# EnCoder.net
KiCad netlist of a schematic drawn in Altium Designer
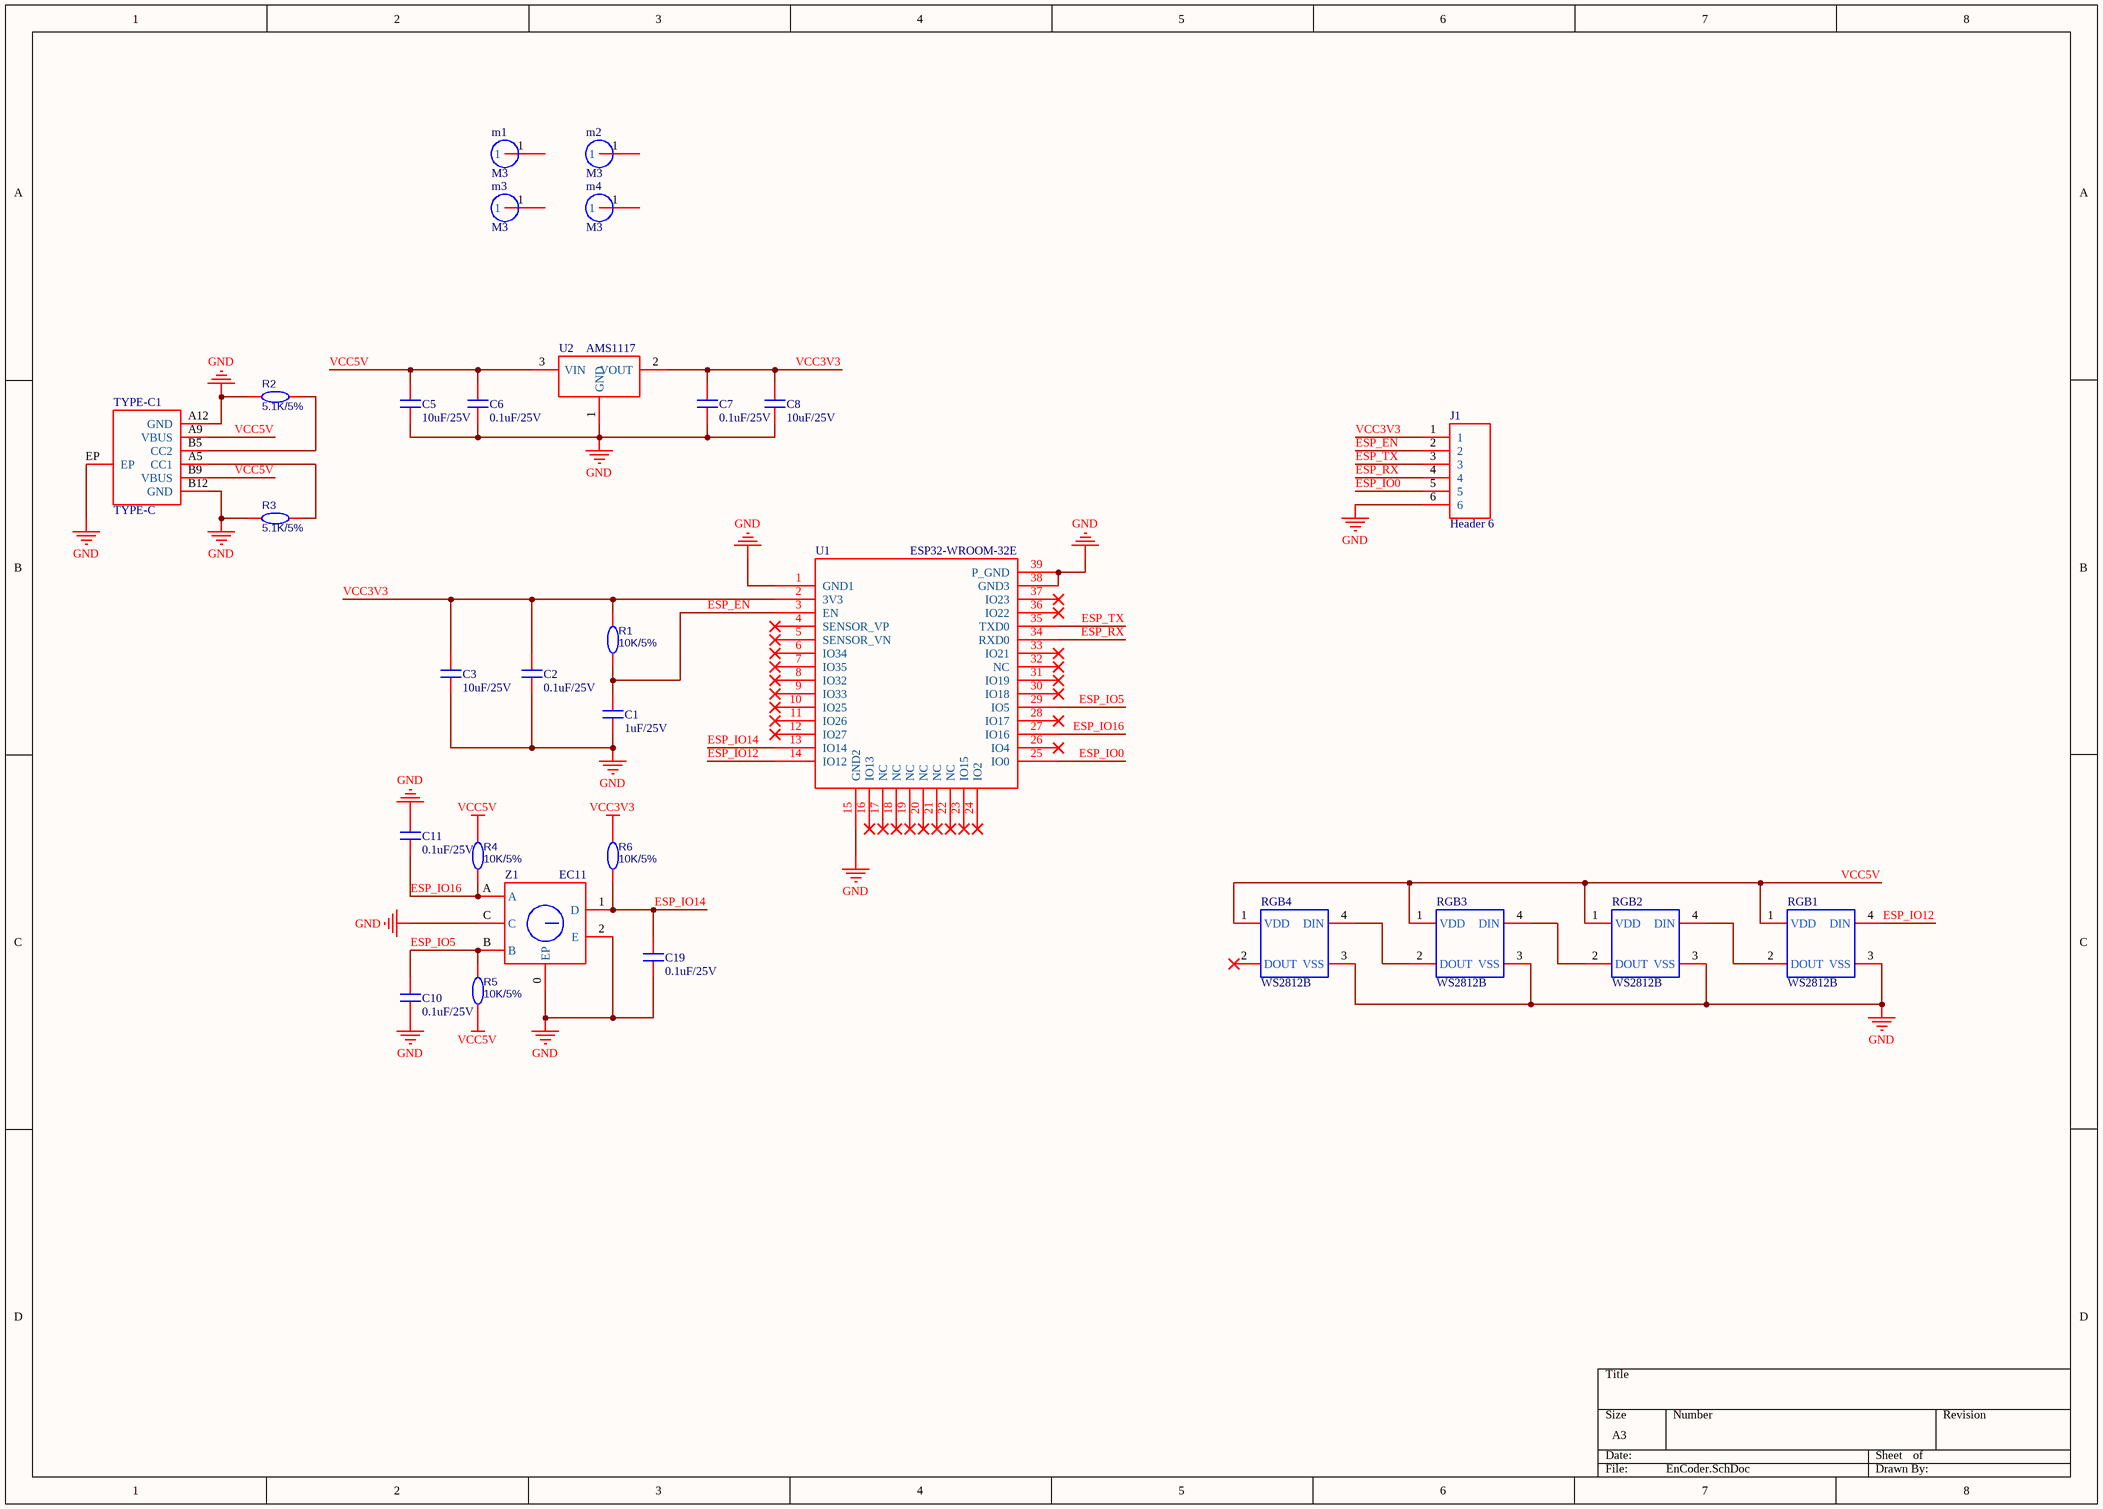
[diagram p0: EnCoder.SchDoc]

(export (version "E")
  (design (tool "Eeschema 10.0.6"))
  (components
    (comp (ref "C1")
      (value "1uF/25V")
      (footprint "C 0805B")
      (description "贴片电容")
      (libsource (lib "COYOO") (part "C 0805"))
    )
    (comp (ref "C2")
      (value "0.1uF/25V")
      (footprint "C 0805B")
      (description "贴片电容")
      (libsource (lib "COYOO") (part "C 0805"))
    )
    (comp (ref "C3")
      (value "10uF/25V")
      (footprint "C 0805B")
      (description "贴片电容")
      (libsource (lib "COYOO") (part "C 0805"))
    )
    (comp (ref "C5")
      (value "10uF/25V")
      (footprint "C 0805B")
      (description "贴片电容")
      (libsource (lib "COYOO") (part "C 0805"))
    )
    (comp (ref "C6")
      (value "0.1uF/25V")
      (footprint "C 0805B")
      (description "贴片电容")
      (libsource (lib "COYOO") (part "C 0805"))
    )
    (comp (ref "C7")
      (value "0.1uF/25V")
      (footprint "C 0805B")
      (description "贴片电容")
      (libsource (lib "COYOO") (part "C 0805"))
    )
    (comp (ref "C8")
      (value "10uF/25V")
      (footprint "C 0805B")
      (description "贴片电容")
      (libsource (lib "COYOO") (part "C 0805"))
    )
    (comp (ref "C10")
      (value "0.1uF/25V")
      (footprint "C 0805B")
      (description "贴片电容")
      (libsource (lib "COYOO") (part "C 0805"))
    )
    (comp (ref "C11")
      (value "0.1uF/25V")
      (footprint "C 0805B")
      (description "贴片电容")
      (libsource (lib "COYOO") (part "C 0805"))
    )
    (comp (ref "C19")
      (value "0.1uF/25V")
      (footprint "C 0805B")
      (description "贴片电容")
      (libsource (lib "COYOO") (part "C 0805"))
    )
    (comp (ref "J1")
      (value "Header 6")
      (footprint "Header6")
      (description "端子")
      (libsource (lib "COYOO") (part "Header 6"))
    )
    (comp (ref "m1") (value "M3") (footprint "M3") (description "M3螺丝") (libsource (lib "COYOO") (part "M3")))
    (comp (ref "m2") (value "M3") (footprint "M3") (description "M3螺丝") (libsource (lib "COYOO") (part "M3")))
    (comp (ref "m3") (value "M3") (footprint "M3") (description "M3螺丝") (libsource (lib "COYOO") (part "M3")))
    (comp (ref "m4") (value "M3") (footprint "M3") (description "M3螺丝") (libsource (lib "COYOO") (part "M3")))
    (comp (ref "R1")
      (value "10K/5%")
      (footprint "R 0805")
      (description "贴片电阻")
      (fields
        (field (name "BOM_MANUFACTURER PART") "RTT021202FTH")
        (field (name "BOM_SUPPLIER PART") "C102781")
      )
      (libsource (lib "COYOO") (part "R 0603"))
    )
    (comp (ref "R2")
      (value "5.1K/5%")
      (footprint "R 0805")
      (description "贴片电阻")
      (fields
        (field (name "BOM_MANUFACTURER PART") "RTT021202FTH")
        (field (name "BOM_SUPPLIER PART") "C102781")
      )
      (libsource (lib "COYOO") (part "R 0603"))
    )
    (comp (ref "R3")
      (value "5.1K/5%")
      (footprint "R 0805")
      (description "贴片电阻")
      (fields
        (field (name "BOM_MANUFACTURER PART") "RTT021202FTH")
        (field (name "BOM_SUPPLIER PART") "C102781")
      )
      (libsource (lib "COYOO") (part "R 0603"))
    )
    (comp (ref "R4")
      (value "10K/5%")
      (footprint "R 0805")
      (description "贴片电阻")
      (fields
        (field (name "BOM_MANUFACTURER PART") "RTT021202FTH")
        (field (name "BOM_SUPPLIER PART") "C102781")
      )
      (libsource (lib "COYOO") (part "R 0603"))
    )
    (comp (ref "R5")
      (value "10K/5%")
      (footprint "R 0805")
      (description "贴片电阻")
      (fields
        (field (name "BOM_MANUFACTURER PART") "RTT021202FTH")
        (field (name "BOM_SUPPLIER PART") "C102781")
      )
      (libsource (lib "COYOO") (part "R 0603"))
    )
    (comp (ref "R6")
      (value "10K/5%")
      (footprint "R 0805")
      (description "贴片电阻")
      (fields
        (field (name "BOM_MANUFACTURER PART") "RTT021202FTH")
        (field (name "BOM_SUPPLIER PART") "C102781")
      )
      (libsource (lib "COYOO") (part "R 0603"))
    )
    (comp (ref "RGB1")
      (value "WS2812B")
      (footprint "RGBLED5050-4")
      (description "WS2812B灯珠")
      (libsource (lib "COYOO") (part "WS2812B"))
    )
    (comp (ref "RGB2")
      (value "WS2812B")
      (footprint "RGBLED5050-4")
      (description "WS2812B灯珠")
      (libsource (lib "COYOO") (part "WS2812B"))
    )
    (comp (ref "RGB3")
      (value "WS2812B")
      (footprint "RGBLED5050-4")
      (description "WS2812B灯珠")
      (libsource (lib "COYOO") (part "WS2812B"))
    )
    (comp (ref "RGB4")
      (value "WS2812B")
      (footprint "RGBLED5050-4")
      (description "WS2812B灯珠")
      (libsource (lib "COYOO") (part "WS2812B"))
    )
    (comp (ref "TYPE-C1")
      (value "TYPE-C")
      (footprint "TYPE-C-6P")
      (libsource (lib "COYOO") (part "TYPE-C-6"))
    )
    (comp (ref "U1")
      (value "ESP32-WROOM-32E")
      (footprint "ESP32-WROOM-32E")
      (description "ESP32模块")
      (libsource (lib "COYOO") (part "ESP32-WROOM-32E"))
    )
    (comp (ref "U2")
      (value "AMS1117")
      (footprint "SOT223_L")
      (description "IC LDO")
      (libsource (lib "COYOO") (part "AMS1117"))
    )
    (comp (ref "Z1")
      (value "EC11")
      (footprint "EC11-SMD")
      (description "编码器")
      (libsource (lib "COYOO") (part "EC11"))
    )
  )
  (nets
    (net (code "1") (name "/ESP_EN") (class "Default")
      (node (ref "C1") (pin "2") (pinfunction "2_2") (pintype "passive"))
      (node (ref "J1") (pin "2") (pinfunction "2_2") (pintype "passive"))
      (node (ref "R1") (pin "1") (pinfunction "1_1") (pintype "passive"))
      (node (ref "U1") (pin "3") (pinfunction "EN_3") (pintype "passive"))
    )
    (net (code "2") (name "/ESP_IO0") (class "Default")
      (node (ref "J1") (pin "5") (pinfunction "5_5") (pintype "passive"))
      (node (ref "U1") (pin "25") (pinfunction "IO0_25") (pintype "passive"))
    )
    (net (code "3") (name "/ESP_IO5") (class "Default")
      (node (ref "C10") (pin "1") (pinfunction "1_1") (pintype "passive"))
      (node (ref "R5") (pin "1") (pinfunction "1_1") (pintype "passive"))
      (node (ref "U1") (pin "29") (pinfunction "IO5_29") (pintype "passive"))
      (node (ref "Z1") (pin "B") (pinfunction "B_B") (pintype "passive"))
    )
    (net (code "4") (name "/ESP_IO12") (class "Default")
      (node (ref "RGB1") (pin "4") (pinfunction "DIN_4") (pintype "passive"))
      (node (ref "U1") (pin "14") (pinfunction "IO12_14") (pintype "passive"))
    )
    (net (code "5") (name "/ESP_IO14") (class "Default")
      (node (ref "C19") (pin "1") (pinfunction "1_1") (pintype "passive"))
      (node (ref "R6") (pin "2") (pinfunction "2_2") (pintype "passive"))
      (node (ref "U1") (pin "13") (pinfunction "IO14_13") (pintype "passive"))
      (node (ref "Z1") (pin "1") (pinfunction "D_1") (pintype "passive"))
    )
    (net (code "6") (name "/ESP_IO16") (class "Default")
      (node (ref "C11") (pin "2") (pinfunction "2_2") (pintype "passive"))
      (node (ref "R4") (pin "2") (pinfunction "2_2") (pintype "passive"))
      (node (ref "U1") (pin "27") (pinfunction "IO16_27") (pintype "passive"))
      (node (ref "Z1") (pin "A") (pinfunction "A_A") (pintype "passive"))
    )
    (net (code "7") (name "/ESP_RX") (class "Default")
      (node (ref "J1") (pin "4") (pinfunction "4_4") (pintype "passive"))
      (node (ref "U1") (pin "34") (pinfunction "RXD0_34") (pintype "passive"))
    )
    (net (code "8") (name "/ESP_TX") (class "Default")
      (node (ref "J1") (pin "3") (pinfunction "3_3") (pintype "passive"))
      (node (ref "U1") (pin "35") (pinfunction "TXD0_35") (pintype "passive"))
    )
    (net (code "9") (name "GND") (class "Default")
      (node (ref "C1") (pin "1") (pinfunction "1_1") (pintype "passive"))
      (node (ref "C10") (pin "2") (pinfunction "2_2") (pintype "passive"))
      (node (ref "C11") (pin "1") (pinfunction "1_1") (pintype "passive"))
      (node (ref "C19") (pin "2") (pinfunction "2_2") (pintype "passive"))
      (node (ref "C2") (pin "1") (pinfunction "1_1") (pintype "passive"))
      (node (ref "C3") (pin "1") (pinfunction "1_1") (pintype "passive"))
      (node (ref "C5") (pin "1") (pinfunction "1_1") (pintype "passive"))
      (node (ref "C6") (pin "1") (pinfunction "1_1") (pintype "passive"))
      (node (ref "C7") (pin "1") (pinfunction "1_1") (pintype "passive"))
      (node (ref "C8") (pin "1") (pinfunction "1_1") (pintype "passive"))
      (node (ref "J1") (pin "6") (pinfunction "6_6") (pintype "passive"))
      (node (ref "R2") (pin "2") (pinfunction "2_2") (pintype "passive"))
      (node (ref "R3") (pin "2") (pinfunction "2_2") (pintype "passive"))
      (node (ref "RGB1") (pin "3") (pinfunction "VSS_3") (pintype "passive"))
      (node (ref "RGB2") (pin "3") (pinfunction "VSS_3") (pintype "passive"))
      (node (ref "RGB3") (pin "3") (pinfunction "VSS_3") (pintype "passive"))
      (node (ref "RGB4") (pin "3") (pinfunction "VSS_3") (pintype "passive"))
      (node (ref "TYPE-C1") (pin "A12") (pinfunction "GND_A12") (pintype "passive"))
      (node (ref "TYPE-C1") (pin "B12") (pinfunction "GND_B12") (pintype "passive"))
      (node (ref "TYPE-C1") (pin "EP") (pinfunction "EP_EP") (pintype "passive"))
      (node (ref "U1") (pin "1") (pinfunction "GND1_1") (pintype "passive"))
      (node (ref "U1") (pin "15") (pinfunction "GND2_15") (pintype "passive"))
      (node (ref "U1") (pin "38") (pinfunction "GND3_38") (pintype "passive"))
      (node (ref "U1") (pin "39") (pinfunction "P_GND_39") (pintype "passive"))
      (node (ref "U2") (pin "1") (pinfunction "GND_1") (pintype "power_in"))
      (node (ref "Z1") (pin "0") (pinfunction "EP_0") (pintype "passive"))
      (node (ref "Z1") (pin "2") (pinfunction "E_2") (pintype "passive"))
      (node (ref "Z1") (pin "C") (pinfunction "C_C") (pintype "passive"))
    )
    (net (code "10") (name "Net-(RGB1-DOUT)") (class "Default")
      (node (ref "RGB1") (pin "2") (pinfunction "DOUT_2") (pintype "passive"))
      (node (ref "RGB2") (pin "4") (pinfunction "DIN_4") (pintype "passive"))
    )
    (net (code "11") (name "Net-(RGB2-DOUT)") (class "Default")
      (node (ref "RGB2") (pin "2") (pinfunction "DOUT_2") (pintype "passive"))
      (node (ref "RGB3") (pin "4") (pinfunction "DIN_4") (pintype "passive"))
    )
    (net (code "12") (name "Net-(RGB3-DOUT)") (class "Default")
      (node (ref "RGB3") (pin "2") (pinfunction "DOUT_2") (pintype "passive"))
      (node (ref "RGB4") (pin "4") (pinfunction "DIN_4") (pintype "passive"))
    )
    (net (code "13") (name "Net-(TYPE-C1-CC1)") (class "Default")
      (node (ref "R3") (pin "1") (pinfunction "1_1") (pintype "passive"))
      (node (ref "TYPE-C1") (pin "A5") (pinfunction "CC1_A5") (pintype "passive"))
    )
    (net (code "14") (name "Net-(TYPE-C1-CC2)") (class "Default")
      (node (ref "R2") (pin "1") (pinfunction "1_1") (pintype "passive"))
      (node (ref "TYPE-C1") (pin "B5") (pinfunction "CC2_B5") (pintype "passive"))
    )
    (net (code "15") (name "VCC3V3") (class "Default")
      (node (ref "C2") (pin "2") (pinfunction "2_2") (pintype "passive"))
      (node (ref "C3") (pin "2") (pinfunction "2_2") (pintype "passive"))
      (node (ref "C7") (pin "2") (pinfunction "2_2") (pintype "passive"))
      (node (ref "C8") (pin "2") (pinfunction "2_2") (pintype "passive"))
      (node (ref "J1") (pin "1") (pinfunction "1_1") (pintype "passive"))
      (node (ref "R1") (pin "2") (pinfunction "2_2") (pintype "passive"))
      (node (ref "R6") (pin "1") (pinfunction "1_1") (pintype "passive"))
      (node (ref "U1") (pin "2") (pinfunction "3V3_2") (pintype "passive"))
      (node (ref "U2") (pin "2") (pinfunction "VOUT_2") (pintype "passive"))
    )
    (net (code "16") (name "VCC5V") (class "Default")
      (node (ref "C5") (pin "2") (pinfunction "2_2") (pintype "passive"))
      (node (ref "C6") (pin "2") (pinfunction "2_2") (pintype "passive"))
      (node (ref "R4") (pin "1") (pinfunction "1_1") (pintype "passive"))
      (node (ref "R5") (pin "2") (pinfunction "2_2") (pintype "passive"))
      (node (ref "RGB1") (pin "1") (pinfunction "VDD_1") (pintype "passive"))
      (node (ref "RGB2") (pin "1") (pinfunction "VDD_1") (pintype "passive"))
      (node (ref "RGB3") (pin "1") (pinfunction "VDD_1") (pintype "passive"))
      (node (ref "RGB4") (pin "1") (pinfunction "VDD_1") (pintype "passive"))
      (node (ref "TYPE-C1") (pin "A9") (pinfunction "VBUS_A9") (pintype "passive"))
      (node (ref "TYPE-C1") (pin "B9") (pinfunction "VBUS_B9") (pintype "passive"))
      (node (ref "U2") (pin "3") (pinfunction "VIN_3") (pintype "passive"))
    )
    (net (code "17") (name "unconnected-(RGB4-DOUT-Pad2)") (class "Default")
      (node (ref "RGB4") (pin "2") (pinfunction "DOUT_2") (pintype "passive+no_connect"))
    )
    (net (code "18") (name "unconnected-(U1-IO2-Pad24)") (class "Default")
      (node (ref "U1") (pin "24") (pinfunction "IO2_24") (pintype "passive+no_connect"))
    )
    (net (code "19") (name "unconnected-(U1-IO4-Pad26)") (class "Default")
      (node (ref "U1") (pin "26") (pinfunction "IO4_26") (pintype "passive+no_connect"))
    )
    (net (code "20") (name "unconnected-(U1-IO13-Pad16)") (class "Default")
      (node (ref "U1") (pin "16") (pinfunction "IO13_16") (pintype "passive+no_connect"))
    )
    (net (code "21") (name "unconnected-(U1-IO15-Pad23)") (class "Default")
      (node (ref "U1") (pin "23") (pinfunction "IO15_23") (pintype "passive+no_connect"))
    )
    (net (code "22") (name "unconnected-(U1-IO17-Pad28)") (class "Default")
      (node (ref "U1") (pin "28") (pinfunction "IO17_28") (pintype "passive+no_connect"))
    )
    (net (code "23") (name "unconnected-(U1-IO18-Pad30)") (class "Default")
      (node (ref "U1") (pin "30") (pinfunction "IO18_30") (pintype "passive+no_connect"))
    )
    (net (code "24") (name "unconnected-(U1-IO19-Pad31)") (class "Default")
      (node (ref "U1") (pin "31") (pinfunction "IO19_31") (pintype "passive+no_connect"))
    )
    (net (code "25") (name "unconnected-(U1-IO21-Pad33)") (class "Default")
      (node (ref "U1") (pin "33") (pinfunction "IO21_33") (pintype "passive+no_connect"))
    )
    (net (code "26") (name "unconnected-(U1-IO22-Pad36)") (class "Default")
      (node (ref "U1") (pin "36") (pinfunction "IO22_36") (pintype "passive+no_connect"))
    )
    (net (code "27") (name "unconnected-(U1-IO23-Pad37)") (class "Default")
      (node (ref "U1") (pin "37") (pinfunction "IO23_37") (pintype "passive+no_connect"))
    )
    (net (code "28") (name "unconnected-(U1-IO25-Pad10)") (class "Default")
      (node (ref "U1") (pin "10") (pinfunction "IO25_10") (pintype "passive+no_connect"))
    )
    (net (code "29") (name "unconnected-(U1-IO26-Pad11)") (class "Default")
      (node (ref "U1") (pin "11") (pinfunction "IO26_11") (pintype "passive+no_connect"))
    )
    (net (code "30") (name "unconnected-(U1-IO27-Pad12)") (class "Default")
      (node (ref "U1") (pin "12") (pinfunction "IO27_12") (pintype "passive+no_connect"))
    )
    (net (code "31") (name "unconnected-(U1-IO32-Pad8)") (class "Default")
      (node (ref "U1") (pin "8") (pinfunction "IO32_8") (pintype "passive+no_connect"))
    )
    (net (code "32") (name "unconnected-(U1-IO33-Pad9)") (class "Default")
      (node (ref "U1") (pin "9") (pinfunction "IO33_9") (pintype "passive+no_connect"))
    )
    (net (code "33") (name "unconnected-(U1-IO34-Pad6)") (class "Default")
      (node (ref "U1") (pin "6") (pinfunction "IO34_6") (pintype "passive+no_connect"))
    )
    (net (code "34") (name "unconnected-(U1-IO35-Pad7)") (class "Default")
      (node (ref "U1") (pin "7") (pinfunction "IO35_7") (pintype "passive+no_connect"))
    )
    (net (code "35") (name "unconnected-(U1-NC-Pad17)") (class "Default")
      (node (ref "U1") (pin "17") (pinfunction "NC_17") (pintype "passive+no_connect"))
    )
    (net (code "36") (name "unconnected-(U1-NC-Pad18)") (class "Default")
      (node (ref "U1") (pin "18") (pinfunction "NC_18") (pintype "passive+no_connect"))
    )
    (net (code "37") (name "unconnected-(U1-NC-Pad19)") (class "Default")
      (node (ref "U1") (pin "19") (pinfunction "NC_19") (pintype "passive+no_connect"))
    )
    (net (code "38") (name "unconnected-(U1-NC-Pad20)") (class "Default")
      (node (ref "U1") (pin "20") (pinfunction "NC_20") (pintype "passive+no_connect"))
    )
    (net (code "39") (name "unconnected-(U1-NC-Pad21)") (class "Default")
      (node (ref "U1") (pin "21") (pinfunction "NC_21") (pintype "passive+no_connect"))
    )
    (net (code "40") (name "unconnected-(U1-NC-Pad22)") (class "Default")
      (node (ref "U1") (pin "22") (pinfunction "NC_22") (pintype "passive+no_connect"))
    )
    (net (code "41") (name "unconnected-(U1-NC-Pad32)") (class "Default")
      (node (ref "U1") (pin "32") (pinfunction "NC_32") (pintype "passive+no_connect"))
    )
    (net (code "42") (name "unconnected-(U1-SENSOR_VN-Pad5)") (class "Default")
      (node (ref "U1") (pin "5") (pinfunction "SENSOR_VN_5") (pintype "passive+no_connect"))
    )
    (net (code "43") (name "unconnected-(U1-SENSOR_VP-Pad4)") (class "Default")
      (node (ref "U1") (pin "4") (pinfunction "SENSOR_VP_4") (pintype "passive+no_connect"))
    )
    (net (code "44") (name "unconnected-(m1-Pad1)") (class "Default")
      (node (ref "m1") (pin "1") (pinfunction "1_1") (pintype "passive"))
    )
    (net (code "45") (name "unconnected-(m2-Pad1)") (class "Default")
      (node (ref "m2") (pin "1") (pinfunction "1_1") (pintype "passive"))
    )
    (net (code "46") (name "unconnected-(m3-Pad1)") (class "Default")
      (node (ref "m3") (pin "1") (pinfunction "1_1") (pintype "passive"))
    )
    (net (code "47") (name "unconnected-(m4-Pad1)") (class "Default")
      (node (ref "m4") (pin "1") (pinfunction "1_1") (pintype "passive"))
    )
  )
)
